# z-probe.net
KiCad netlist of a schematic drawn in Altium Designer
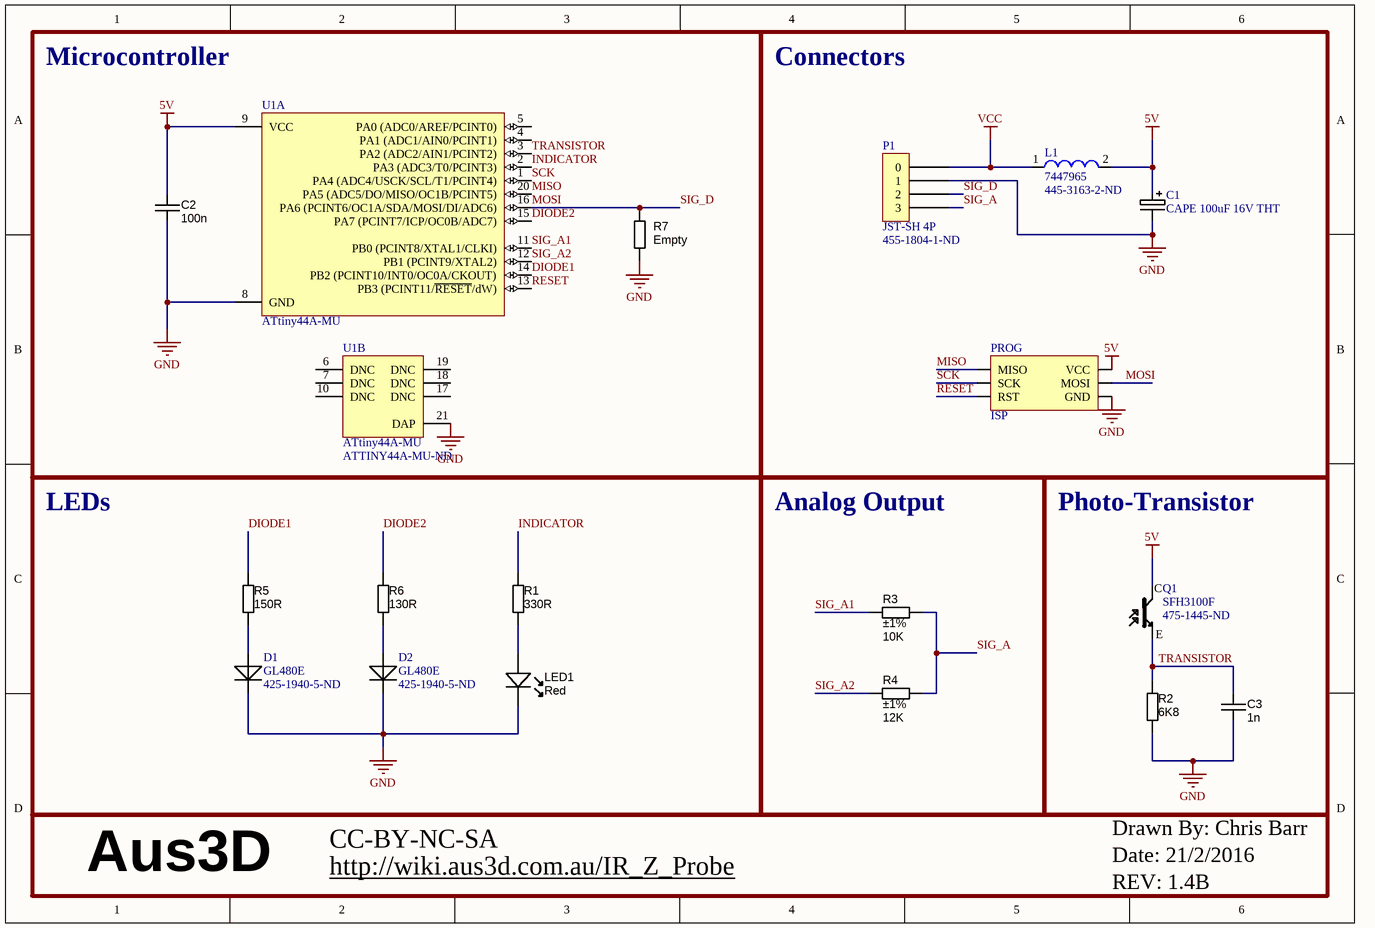
[diagram p0: z-probe.SchDoc]

(export (version "E")
  (design (tool "Eeschema 10.0.6"))
  (components
    (comp (ref "C1")
      (value "CAPE 100uF 16V THT")
      (footprint "6-DIA-CAP")
      (libsource (lib "Schlib1") (part "CAPE 100uF 16V THT"))
    )
    (comp (ref "C2")
      (value "100n")
      (footprint "CAPC1608X90N")
      (description "Capacitor SMD Cer 100nF 10% 50V X7R 0603")
      (fields (field (name "TOLERANCE") "±10%") (field (name "Comment") "approved sub OK"))
      (libsource (lib "PBL - Capacitors") (part "CAPC_100n_0603_X7R_50V_10%"))
    )
    (comp (ref "C3")
      (value "1n")
      (footprint "CAPC1608X90N")
      (description "Capacitor SMD Cer 1nF 10% 100V X7R 0603")
      (fields (field (name "TOLERANCE") "±10%") (field (name "Comment") "approved sub OK"))
      (libsource (lib "PBL - Capacitors") (part "CAPC_1n_0603_X7R_100V_10%"))
    )
    (comp (ref "D1")
      (value "GL480E")
      (footprint "PcbLib1:LED-2.54spacing")
      (fields (field (name "SUPPLIER PART NUMBER 1") "425-1940-5-ND"))
      (libsource (lib "Schlib1") (part "GL480E"))
    )
    (comp (ref "D2")
      (value "GL480E")
      (footprint "PcbLib1:LED-2.54spacing")
      (fields (field (name "SUPPLIER PART NUMBER 1") "425-1940-5-ND"))
      (libsource (lib "Schlib1") (part "GL480E"))
    )
    (comp (ref "L1")
      (value "7447965")
      (footprint "SMD-0603")
      (description "SMD-Multilayer Inductor WE-MI, L = 1.00 µH")
      (fields (field (name "SUPPLIER PART NUMBER 1") "445-3163-2-ND"))
      (libsource (lib "Filter Inductor") (part "7447965"))
    )
    (comp (ref "LED1")
      (value "Red")
      (footprint "LED-0603-RED")
      (description "LED 0603 SMD Hyper Red 630nm 220mcd 20mA")
      (libsource (lib "PBL - Light Sources") (part "LED_SMD_Red_0603_220mcd"))
    )
    (comp (ref "P1")
      (value "JST-SH 4P")
      (footprint "SM04B-SRSS-TB")
      (fields (field (name "SUPPLIER PART NUMBER 1") "455-1804-1-ND"))
      (libsource (lib "Schlib1") (part "SM04B-SRSS-TB"))
    )
    (comp (ref "PROG") (value "ISP") (footprint "ICSP Pads") (libsource (lib "Schlib1") (part "ISP Header")))
    (comp (ref "Q1")
      (value "SFH3100F")
      (footprint "SFH3100F-footprint")
      (fields (field (name "SUPPLIER PART NUMBER 1") "475-1445-ND"))
      (libsource (lib "Schlib1") (part "SFH3100F"))
    )
    (comp (ref "R1")
      (value "330R")
      (footprint "RESC1608X55N")
      (description "Resistor SMD chip 330 Ohm 0.1W 5% 0603")
      (fields (field (name "TOLERANCE") "±5%") (field (name "Comment") "Thick Film"))
      (libsource (lib "PBL - Resistors") (part "RES_330R_0603_5%"))
    )
    (comp (ref "R2")
      (value "6K8")
      (footprint "RESC1608X55N")
      (description "Resistor SMD chip 2.2k Ohm 0.1W 5% 0603")
      (fields (field (name "TOLERANCE") "±5%") (field (name "Comment") "Thick Film"))
      (libsource (lib "PBL - Resistors") (part "RES_2K2_0603_5%"))
    )
    (comp (ref "R3")
      (value "10K")
      (footprint "RESC1608X55N")
      (description "Resistor SMD chip 10k Ohm 0.1W 1% 0603")
      (fields (field (name "TOLERANCE") "±1%") (field (name "Comment") "Thick Film"))
      (libsource (lib "PBL - Resistors") (part "RES_10K_0603_1%"))
    )
    (comp (ref "R4")
      (value "12K")
      (footprint "RESC1608X55N")
      (description "Resistor SMD chip 10k Ohm 0.1W 1% 0603")
      (fields (field (name "TOLERANCE") "±1%") (field (name "Comment") "Thick Film"))
      (libsource (lib "PBL - Resistors") (part "RES_10K_0603_1%"))
    )
    (comp (ref "R5")
      (value "150R")
      (footprint "RESC1608X55N")
      (description "Resistor SMD chip 2.2k Ohm 0.1W 5% 0603")
      (fields (field (name "TOLERANCE") "±5%") (field (name "Comment") "Thick Film"))
      (libsource (lib "PBL - Resistors") (part "RES_2K2_0603_5%"))
    )
    (comp (ref "R6")
      (value "130R")
      (footprint "RESC1608X55N")
      (description "Resistor SMD chip 2.2k Ohm 0.1W 5% 0603")
      (fields (field (name "TOLERANCE") "±5%") (field (name "Comment") "Thick Film"))
      (libsource (lib "PBL - Resistors") (part "RES_2K2_0603_5%"))
    )
    (comp (ref "R7")
      (value "Empty")
      (footprint "RESC2012X70N")
      (description "Resistor, 0805 SMD, Empty footprint")
      (libsource (lib "PBL - Resistors") (part "RES_EMPTY_0805"))
    )
    (comp (ref "U1")
      (value "ATtiny44A-MU")
      (footprint "20M1_N")
      (fields (field (name "SUPPLIER PART NUMBER 1") "ATTINY44A-MU-ND"))
      (libsource (lib "Microcontroller tinyAVR") (part "ATtiny44A-MU"))
    )
  )
  (nets
    (net (code "1") (name "/DIODE1") (class "Default")
      (node (ref "R5") (pin "2") (pinfunction "2_2") (pintype "passive"))
      (node (ref "U1") (pin "14") (pinfunction "PB2_(PCINT10/INT0/OC0A/CKOUT)_14") (pintype "bidirectional"))
    )
    (net (code "2") (name "/DIODE2") (class "Default")
      (node (ref "R6") (pin "2") (pinfunction "2_2") (pintype "passive"))
      (node (ref "U1") (pin "15") (pinfunction "PA7_(PCINT7/ICP/OC0B/ADC7)_15") (pintype "bidirectional"))
    )
    (net (code "3") (name "/INDICATOR") (class "Default")
      (node (ref "R1") (pin "1") (pinfunction "1_1") (pintype "passive"))
      (node (ref "U1") (pin "2") (pinfunction "PA3_(ADC3/T0/PCINT3)_2") (pintype "bidirectional"))
    )
    (net (code "4") (name "/MISO") (class "Default")
      (node (ref "PROG") (pin "0") (pinfunction "MISO_0") (pintype "passive"))
      (node (ref "U1") (pin "20") (pinfunction "PA5_(ADC5/DO/MISO/OC1B/PCINT5)_20") (pintype "bidirectional"))
    )
    (net (code "5") (name "/MOSI") (class "Default")
      (node (ref "P1") (pin "2") (pinfunction "2_2") (pintype "passive"))
      (node (ref "PROG") (pin "3") (pinfunction "MOSI_3") (pintype "passive"))
      (node (ref "R7") (pin "1") (pinfunction "1_1") (pintype "passive"))
      (node (ref "U1") (pin "16") (pinfunction "PA6_(PCINT6/OC1A/SDA/MOSI/DI/ADC6)_16") (pintype "bidirectional"))
    )
    (net (code "6") (name "/RESET") (class "Default")
      (node (ref "PROG") (pin "4") (pinfunction "RST_4") (pintype "passive"))
      (node (ref "U1") (pin "13") (pinfunction "PB3_(PCINT11/~{RESET}/dW)_13") (pintype "bidirectional"))
    )
    (net (code "7") (name "/SCK") (class "Default")
      (node (ref "PROG") (pin "2") (pinfunction "SCK_2") (pintype "passive"))
      (node (ref "U1") (pin "1") (pinfunction "PA4_(ADC4/USCK/SCL/T1/PCINT4)_1") (pintype "bidirectional"))
    )
    (net (code "8") (name "/SIG_A") (class "Default")
      (node (ref "P1") (pin "3") (pinfunction "3_3") (pintype "passive"))
      (node (ref "R3") (pin "2") (pinfunction "2_2") (pintype "passive"))
      (node (ref "R4") (pin "2") (pinfunction "2_2") (pintype "passive"))
    )
    (net (code "9") (name "/SIG_A1") (class "Default")
      (node (ref "R3") (pin "1") (pinfunction "1_1") (pintype "passive"))
      (node (ref "U1") (pin "11") (pinfunction "PB0_(PCINT8/XTAL1/CLKI)_11") (pintype "bidirectional"))
    )
    (net (code "10") (name "/SIG_A2") (class "Default")
      (node (ref "R4") (pin "1") (pinfunction "1_1") (pintype "passive"))
      (node (ref "U1") (pin "12") (pinfunction "PB1_(PCINT9/XTAL2)_12") (pintype "bidirectional"))
    )
    (net (code "11") (name "/TRANSISTOR") (class "Default")
      (node (ref "C3") (pin "1") (pintype "passive"))
      (node (ref "Q1") (pin "2") (pinfunction "2_2") (pintype "passive"))
      (node (ref "R2") (pin "2") (pinfunction "2_2") (pintype "passive"))
      (node (ref "U1") (pin "3") (pinfunction "PA2_(ADC2/AIN1/PCINT2)_3") (pintype "bidirectional"))
    )
    (net (code "12") (name "5V") (class "Default")
      (node (ref "C1") (pin "1") (pintype "passive"))
      (node (ref "C2") (pin "2") (pintype "passive"))
      (node (ref "L1") (pin "2") (pinfunction "2_2") (pintype "passive"))
      (node (ref "PROG") (pin "1") (pinfunction "VCC_1") (pintype "passive"))
      (node (ref "Q1") (pin "1") (pinfunction "1_1") (pintype "passive"))
      (node (ref "U1") (pin "9") (pinfunction "VCC_9") (pintype "power_in"))
    )
    (net (code "13") (name "GND") (class "Default")
      (node (ref "C1") (pin "0") (pintype "passive"))
      (node (ref "C2") (pin "1") (pintype "passive"))
      (node (ref "C3") (pin "2") (pintype "passive"))
      (node (ref "D1") (pin "1") (pinfunction "1_1") (pintype "passive"))
      (node (ref "D2") (pin "1") (pinfunction "1_1") (pintype "passive"))
      (node (ref "LED1") (pin "K") (pinfunction "K_K") (pintype "passive"))
      (node (ref "P1") (pin "1") (pinfunction "1_1") (pintype "passive"))
      (node (ref "PROG") (pin "5") (pinfunction "GND_5") (pintype "passive"))
      (node (ref "R2") (pin "1") (pinfunction "1_1") (pintype "passive"))
      (node (ref "R7") (pin "2") (pinfunction "2_2") (pintype "passive"))
      (node (ref "U1") (pin "21") (pinfunction "DAP_21") (pintype "power_in"))
      (node (ref "U1") (pin "8") (pinfunction "GND_8") (pintype "power_in"))
    )
    (net (code "14") (name "Net-(D1-Pad2)") (class "Default")
      (node (ref "D1") (pin "2") (pinfunction "2_2") (pintype "passive"))
      (node (ref "R5") (pin "1") (pinfunction "1_1") (pintype "passive"))
    )
    (net (code "15") (name "Net-(D2-Pad2)") (class "Default")
      (node (ref "D2") (pin "2") (pinfunction "2_2") (pintype "passive"))
      (node (ref "R6") (pin "1") (pinfunction "1_1") (pintype "passive"))
    )
    (net (code "16") (name "Net-(LED1-PadA)") (class "Default")
      (node (ref "LED1") (pin "A") (pinfunction "A_A") (pintype "passive"))
      (node (ref "R1") (pin "2") (pinfunction "2_2") (pintype "passive"))
    )
    (net (code "17") (name "VCC") (class "Default")
      (node (ref "L1") (pin "1") (pinfunction "1_1") (pintype "passive"))
      (node (ref "P1") (pin "0") (pinfunction "0_0") (pintype "passive"))
    )
    (net (code "18") (name "unconnected-(U1A-PA0_(ADC0{slash}AREF{slash}PCINT0)-Pad5)") (class "Default")
      (node (ref "U1") (pin "5") (pinfunction "PA0_(ADC0/AREF/PCINT0)_5") (pintype "bidirectional"))
    )
    (net (code "19") (name "unconnected-(U1A-PA1_(ADC1{slash}AIN0{slash}PCINT1)-Pad4)") (class "Default")
      (node (ref "U1") (pin "4") (pinfunction "PA1_(ADC1/AIN0/PCINT1)_4") (pintype "bidirectional"))
    )
    (net (code "20") (name "unconnected-(U1B-DNC-Pad6)") (class "Default")
      (node (ref "U1") (pin "6") (pinfunction "DNC_6") (pintype "passive"))
    )
    (net (code "21") (name "unconnected-(U1B-DNC-Pad7)") (class "Default")
      (node (ref "U1") (pin "7") (pinfunction "DNC_7") (pintype "passive"))
    )
    (net (code "22") (name "unconnected-(U1B-DNC-Pad10)") (class "Default")
      (node (ref "U1") (pin "10") (pinfunction "DNC_10") (pintype "passive"))
    )
    (net (code "23") (name "unconnected-(U1B-DNC-Pad17)") (class "Default")
      (node (ref "U1") (pin "17") (pinfunction "DNC_17") (pintype "passive"))
    )
    (net (code "24") (name "unconnected-(U1B-DNC-Pad18)") (class "Default")
      (node (ref "U1") (pin "18") (pinfunction "DNC_18") (pintype "passive"))
    )
    (net (code "25") (name "unconnected-(U1B-DNC-Pad19)") (class "Default")
      (node (ref "U1") (pin "19") (pinfunction "DNC_19") (pintype "passive"))
    )
  )
)
